# POE_PD_1_P-Schalter.net
KiCad netlist of a schematic drawn in EAGLE
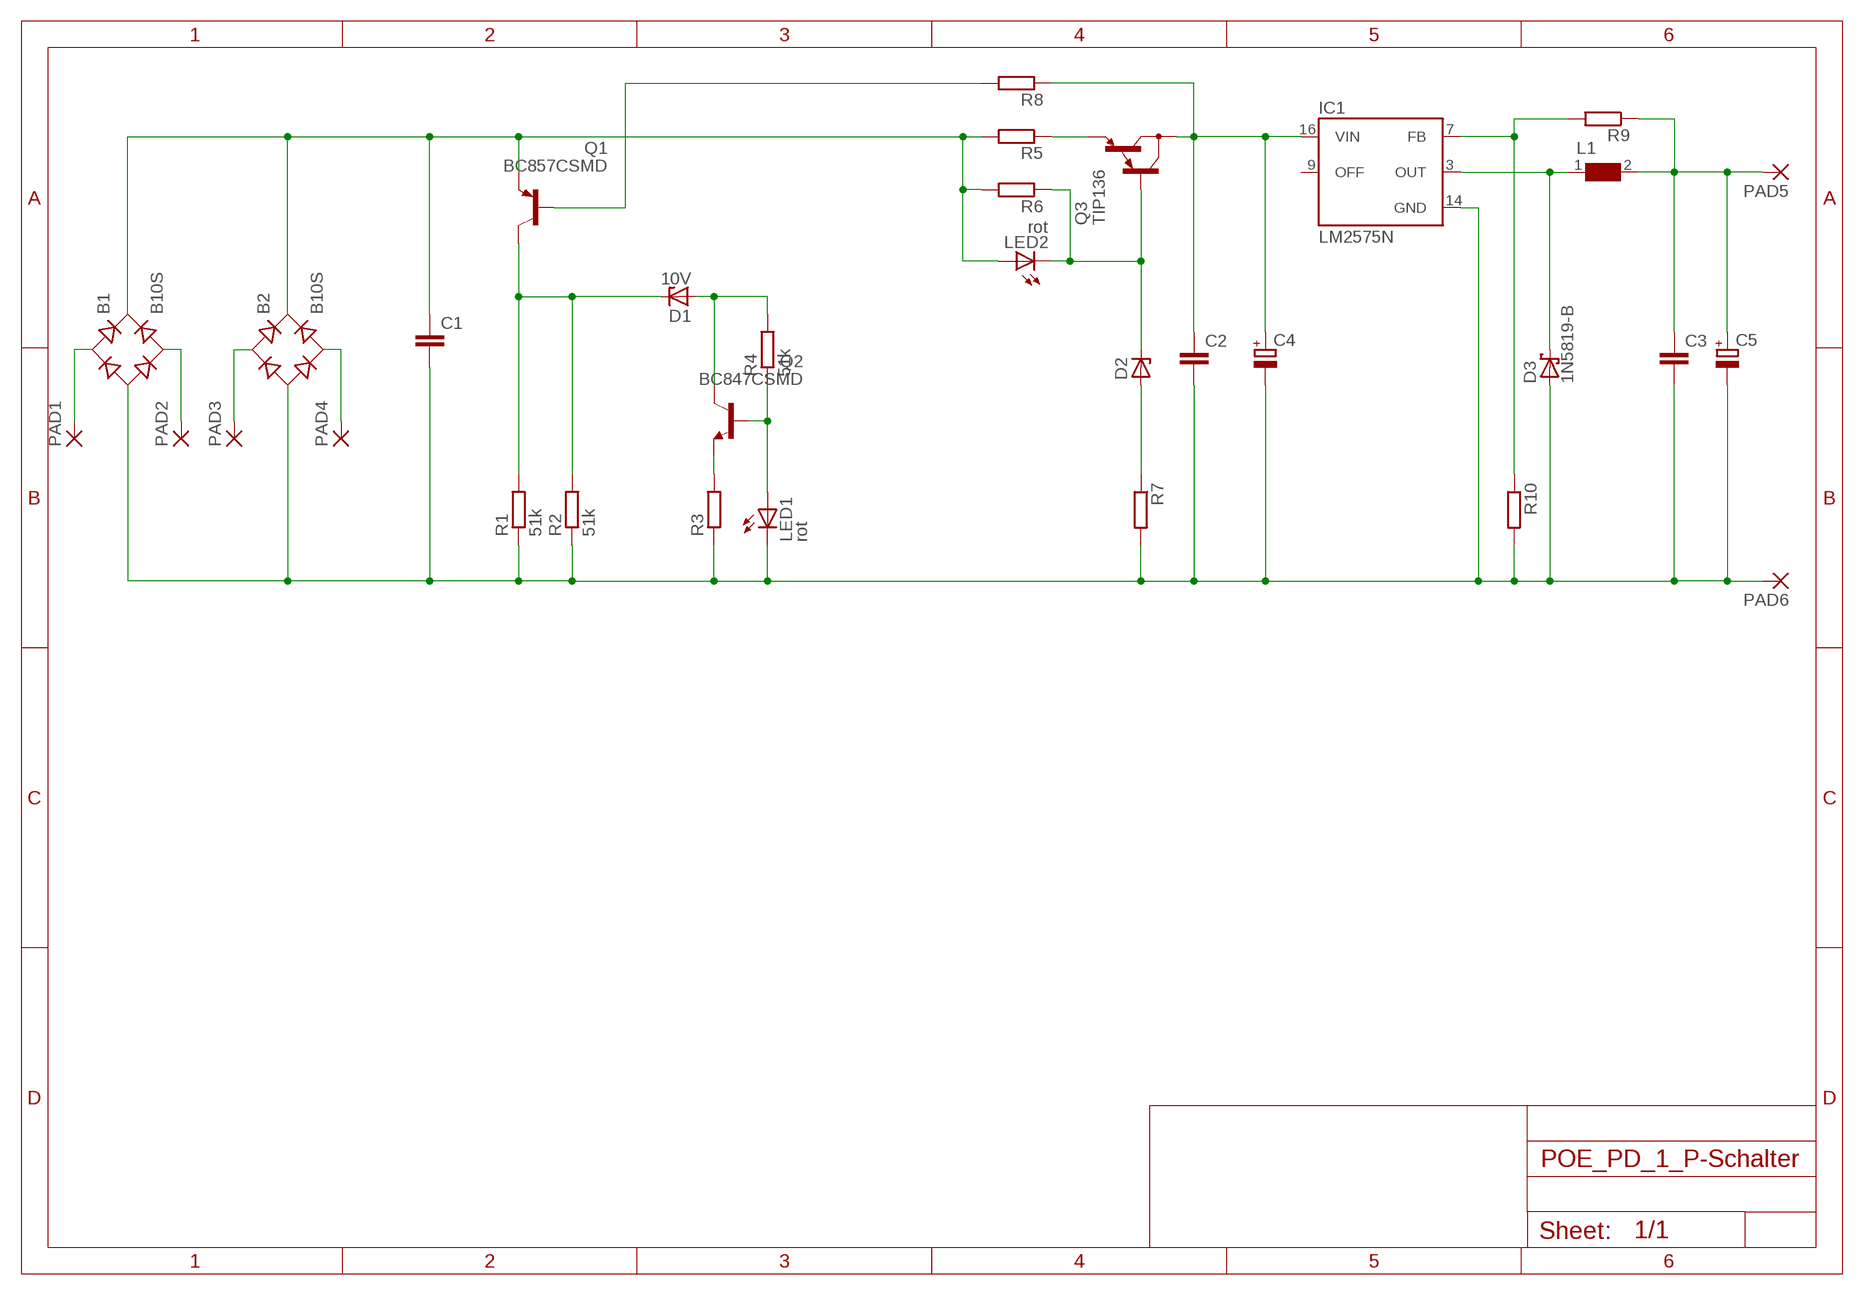
[diagram p0: schematic, sheet 1]

(export (version "E")
  (design (tool "Eeschema 10.0.6"))
  (components
    (comp (ref "B1")
      (value "B10S")
      (footprint "eagle-import:MBS")
      (libsource (lib "eagle-import") (part "BS10"))
    )
    (comp (ref "B2")
      (value "B10S")
      (footprint "eagle-import:MBS")
      (libsource (lib "eagle-import") (part "BS10"))
    )
    (comp (ref "C1")
      (value "C-EUC0805")
      (footprint "eagle-import:C0805")
      (libsource (lib "eagle-import") (part "C-EUC0805"))
    )
    (comp (ref "C2")
      (value "C-EUC0805")
      (footprint "eagle-import:C0805")
      (libsource (lib "eagle-import") (part "C-EUC0805"))
    )
    (comp (ref "C3")
      (value "C-EUC0805")
      (footprint "eagle-import:C0805")
      (libsource (lib "eagle-import") (part "C-EUC0805"))
    )
    (comp (ref "C4")
      (value "CPOL-EU153CLV-0807")
      (footprint "eagle-import:153CLV-0807")
      (libsource (lib "eagle-import") (part "CPOL-EU153CLV-0807"))
    )
    (comp (ref "C5")
      (value "CPOL-EU153CLV-0807")
      (footprint "eagle-import:153CLV-0807")
      (libsource (lib "eagle-import") (part "CPOL-EU153CLV-0807"))
    )
    (comp (ref "D1")
      (value "10V")
      (footprint "eagle-import:SOT23")
      (libsource (lib "eagle-import") (part "ZENER-DIODESOT23"))
    )
    (comp (ref "D2")
      (value "ZENER-DIODESOT23")
      (footprint "eagle-import:SOT23")
      (libsource (lib "eagle-import") (part "ZENER-DIODESOT23"))
    )
    (comp (ref "D3")
      (value "1N5819-B")
      (footprint "eagle-import:DO41-7.6")
      (libsource (lib "eagle-import") (part "1N5819-B"))
    )
    (comp (ref "IC1")
      (value "LM2575N")
      (footprint "eagle-import:DIL16")
      (libsource (lib "eagle-import") (part "LM2575N"))
    )
    (comp (ref "L1")
      (value "WE-PD2_S")
      (footprint "eagle-import:WE-PD2_S")
      (libsource (lib "eagle-import") (part "WE-PD2_S"))
    )
    (comp (ref "LED1")
      (value "rot")
      (footprint "eagle-import:CHIP-LED0805")
      (libsource (lib "eagle-import") (part "LEDCHIP-LED0805"))
    )
    (comp (ref "LED2")
      (value "rot")
      (footprint "eagle-import:CHIP-LED0805")
      (libsource (lib "eagle-import") (part "LEDCHIP-LED0805"))
    )
    (comp (ref "PAD1")
      (value "2,15/1,0")
      (footprint "eagle-import:2,15_1,0")
      (libsource (lib "eagle-import") (part "2,15/1,0"))
    )
    (comp (ref "PAD2")
      (value "2,15/1,0")
      (footprint "eagle-import:2,15_1,0")
      (libsource (lib "eagle-import") (part "2,15/1,0"))
    )
    (comp (ref "PAD3")
      (value "2,15/1,0")
      (footprint "eagle-import:2,15_1,0")
      (libsource (lib "eagle-import") (part "2,15/1,0"))
    )
    (comp (ref "PAD4")
      (value "2,15/1,0")
      (footprint "eagle-import:2,15_1,0")
      (libsource (lib "eagle-import") (part "2,15/1,0"))
    )
    (comp (ref "PAD5")
      (value "2,15/1,0")
      (footprint "eagle-import:2,15_1,0")
      (libsource (lib "eagle-import") (part "2,15/1,0"))
    )
    (comp (ref "PAD6")
      (value "2,15/1,0")
      (footprint "eagle-import:2,15_1,0")
      (libsource (lib "eagle-import") (part "2,15/1,0"))
    )
    (comp (ref "Q1")
      (value "BC857CSMD")
      (footprint "eagle-import:SOT23-BEC")
      (libsource (lib "eagle-import") (part "BC857SMDC"))
    )
    (comp (ref "Q2")
      (value "BC847CSMD")
      (footprint "eagle-import:SOT23")
      (libsource (lib "eagle-import") (part "BC847SMDC"))
    )
    (comp (ref "Q3")
      (value "TIP136")
      (footprint "eagle-import:TO220")
      (libsource (lib "eagle-import") (part "TIP136"))
    )
    (comp (ref "R1")
      (value "51k")
      (footprint "eagle-import:R0603")
      (libsource (lib "eagle-import") (part "R-EU_R0603"))
    )
    (comp (ref "R2")
      (value "51k")
      (footprint "eagle-import:R0603")
      (libsource (lib "eagle-import") (part "R-EU_R0603"))
    )
    (comp (ref "R3")
      (value "R-EU_R0603")
      (footprint "eagle-import:R0603")
      (libsource (lib "eagle-import") (part "R-EU_R0603"))
    )
    (comp (ref "R4")
      (value "51k")
      (footprint "eagle-import:R0603")
      (libsource (lib "eagle-import") (part "R-EU_R0603"))
    )
    (comp (ref "R5")
      (value "R-EU_R0603")
      (footprint "eagle-import:R0603")
      (libsource (lib "eagle-import") (part "R-EU_R0603"))
    )
    (comp (ref "R6")
      (value "R-EU_R0603")
      (footprint "eagle-import:R0603")
      (libsource (lib "eagle-import") (part "R-EU_R0603"))
    )
    (comp (ref "R7")
      (value "R-EU_R0603")
      (footprint "eagle-import:R0603")
      (libsource (lib "eagle-import") (part "R-EU_R0603"))
    )
    (comp (ref "R8")
      (value "R-EU_R0603")
      (footprint "eagle-import:R0603")
      (libsource (lib "eagle-import") (part "R-EU_R0603"))
    )
    (comp (ref "R9")
      (value "R-EU_R0603")
      (footprint "eagle-import:R0603")
      (libsource (lib "eagle-import") (part "R-EU_R0603"))
    )
    (comp (ref "R10")
      (value "R-EU_R0603")
      (footprint "eagle-import:R0603")
      (libsource (lib "eagle-import") (part "R-EU_R0603"))
    )
  )
  (nets
    (net (code "1") (name "Net-(B1-Pad+)") (class "Default")
      (node (ref "B1") (pin "+") (pinfunction "+_+") (pintype "passive"))
      (node (ref "B2") (pin "+") (pinfunction "+_+") (pintype "passive"))
      (node (ref "C1") (pin "1") (pinfunction "1_1") (pintype "passive"))
      (node (ref "LED2") (pin "A") (pinfunction "A_A") (pintype "passive"))
      (node (ref "Q1") (pin "E") (pinfunction "E_E") (pintype "passive"))
      (node (ref "R5") (pin "2") (pinfunction "2_2") (pintype "passive"))
      (node (ref "R6") (pin "2") (pinfunction "2_2") (pintype "passive"))
    )
    (net (code "2") (name "Net-(D1-A)") (class "Default")
      (node (ref "D1") (pin "1") (pinfunction "A_1") (pintype "passive"))
      (node (ref "Q2") (pin "3") (pinfunction "C_3") (pintype "passive"))
      (node (ref "R4") (pin "2") (pinfunction "2_2") (pintype "passive"))
    )
    (net (code "3") (name "Net-(D1-C)") (class "Default")
      (node (ref "D1") (pin "3") (pinfunction "C_3") (pintype "passive"))
      (node (ref "Q1") (pin "C") (pinfunction "C_C") (pintype "passive"))
      (node (ref "R1") (pin "2") (pinfunction "2_2") (pintype "passive"))
      (node (ref "R2") (pin "2") (pinfunction "2_2") (pintype "passive"))
    )
    (net (code "4") (name "Net-(D2-A)") (class "Default")
      (node (ref "D2") (pin "1") (pinfunction "A_1") (pintype "passive"))
      (node (ref "R7") (pin "1") (pinfunction "1_1") (pintype "passive"))
    )
    (net (code "5") (name "Net-(D2-C)") (class "Default")
      (node (ref "D2") (pin "3") (pinfunction "C_3") (pintype "passive"))
      (node (ref "LED2") (pin "C") (pinfunction "C_C") (pintype "passive"))
      (node (ref "Q3") (pin "1") (pinfunction "B_1") (pintype "passive"))
      (node (ref "R6") (pin "1") (pinfunction "1_1") (pintype "passive"))
    )
    (net (code "6") (name "Net-(IC1-FB)") (class "Default")
      (node (ref "IC1") (pin "7") (pinfunction "FB_7") (pintype "input"))
      (node (ref "R10") (pin "1") (pinfunction "1_1") (pintype "passive"))
      (node (ref "R9") (pin "2") (pinfunction "2_2") (pintype "passive"))
    )
    (net (code "7") (name "Net-(IC1-GND)") (class "Default")
      (node (ref "B1") (pin "-") (pinfunction "-_-") (pintype "passive"))
      (node (ref "B2") (pin "-") (pinfunction "-_-") (pintype "passive"))
      (node (ref "C1") (pin "2") (pinfunction "2_2") (pintype "passive"))
      (node (ref "C2") (pin "2") (pinfunction "2_2") (pintype "passive"))
      (node (ref "C3") (pin "2") (pinfunction "2_2") (pintype "passive"))
      (node (ref "C4") (pin "-") (pinfunction "-_-") (pintype "passive"))
      (node (ref "C5") (pin "-") (pinfunction "-_-") (pintype "passive"))
      (node (ref "D3") (pin "A") (pinfunction "A_A") (pintype "passive"))
      (node (ref "IC1") (pin "14") (pinfunction "GND_14") (pintype "power_in"))
      (node (ref "LED1") (pin "C") (pinfunction "C_C") (pintype "passive"))
      (node (ref "PAD6") (pin "1") (pinfunction "P_1") (pintype "passive"))
      (node (ref "R1") (pin "1") (pinfunction "1_1") (pintype "passive"))
      (node (ref "R10") (pin "2") (pinfunction "2_2") (pintype "passive"))
      (node (ref "R2") (pin "1") (pinfunction "1_1") (pintype "passive"))
      (node (ref "R3") (pin "1") (pinfunction "1_1") (pintype "passive"))
      (node (ref "R7") (pin "2") (pinfunction "2_2") (pintype "passive"))
    )
    (net (code "8") (name "Net-(IC1-OUT)") (class "Default")
      (node (ref "D3") (pin "C") (pinfunction "C_C") (pintype "passive"))
      (node (ref "IC1") (pin "3") (pinfunction "OUT_3") (pintype "output"))
      (node (ref "L1") (pin "1") (pinfunction "1_1") (pintype "passive"))
    )
    (net (code "9") (name "Net-(IC1-VIN)") (class "Default")
      (node (ref "C2") (pin "1") (pinfunction "1_1") (pintype "passive"))
      (node (ref "C4") (pin "+") (pinfunction "+_+") (pintype "passive"))
      (node (ref "IC1") (pin "16") (pinfunction "VIN_16") (pintype "power_in"))
      (node (ref "Q3") (pin "2") (pinfunction "C_2") (pintype "passive"))
      (node (ref "R8") (pin "1") (pinfunction "1_1") (pintype "passive"))
    )
    (net (code "10") (name "Net-(PAD1-P)") (class "Default")
      (node (ref "B1") (pin "AC1") (pinfunction "AC1_AC1") (pintype "passive"))
      (node (ref "PAD1") (pin "1") (pinfunction "P_1") (pintype "passive"))
    )
    (net (code "11") (name "Net-(PAD2-P)") (class "Default")
      (node (ref "B1") (pin "AC2") (pinfunction "AC2_AC2") (pintype "passive"))
      (node (ref "PAD2") (pin "1") (pinfunction "P_1") (pintype "passive"))
    )
    (net (code "12") (name "Net-(PAD3-P)") (class "Default")
      (node (ref "B2") (pin "AC1") (pinfunction "AC1_AC1") (pintype "passive"))
      (node (ref "PAD3") (pin "1") (pinfunction "P_1") (pintype "passive"))
    )
    (net (code "13") (name "Net-(PAD4-P)") (class "Default")
      (node (ref "B2") (pin "AC2") (pinfunction "AC2_AC2") (pintype "passive"))
      (node (ref "PAD4") (pin "1") (pinfunction "P_1") (pintype "passive"))
    )
    (net (code "14") (name "Net-(PAD5-P)") (class "Default")
      (node (ref "C3") (pin "1") (pinfunction "1_1") (pintype "passive"))
      (node (ref "C5") (pin "+") (pinfunction "+_+") (pintype "passive"))
      (node (ref "L1") (pin "2") (pinfunction "2_2") (pintype "passive"))
      (node (ref "PAD5") (pin "1") (pinfunction "P_1") (pintype "passive"))
      (node (ref "R9") (pin "1") (pinfunction "1_1") (pintype "passive"))
    )
    (net (code "15") (name "Net-(Q1-PadB)") (class "Default")
      (node (ref "Q1") (pin "B") (pinfunction "B_B") (pintype "passive"))
      (node (ref "R8") (pin "2") (pinfunction "2_2") (pintype "passive"))
    )
    (net (code "16") (name "Net-(Q2-B)") (class "Default")
      (node (ref "LED1") (pin "A") (pinfunction "A_A") (pintype "passive"))
      (node (ref "Q2") (pin "1") (pinfunction "B_1") (pintype "passive"))
      (node (ref "R4") (pin "1") (pinfunction "1_1") (pintype "passive"))
    )
    (net (code "17") (name "Net-(Q2-E)") (class "Default")
      (node (ref "Q2") (pin "2") (pinfunction "E_2") (pintype "passive"))
      (node (ref "R3") (pin "2") (pinfunction "2_2") (pintype "passive"))
    )
    (net (code "18") (name "Net-(Q3-E)") (class "Default")
      (node (ref "Q3") (pin "3") (pinfunction "E_3") (pintype "passive"))
      (node (ref "R5") (pin "1") (pinfunction "1_1") (pintype "passive"))
    )
    (net (code "19") (name "unconnected-(IC1-OFF-Pad9)") (class "Default")
      (node (ref "IC1") (pin "9") (pinfunction "OFF_9") (pintype "input"))
    )
  )
)
